# LED.net
KiCad netlist of a schematic drawn in Altium Designer
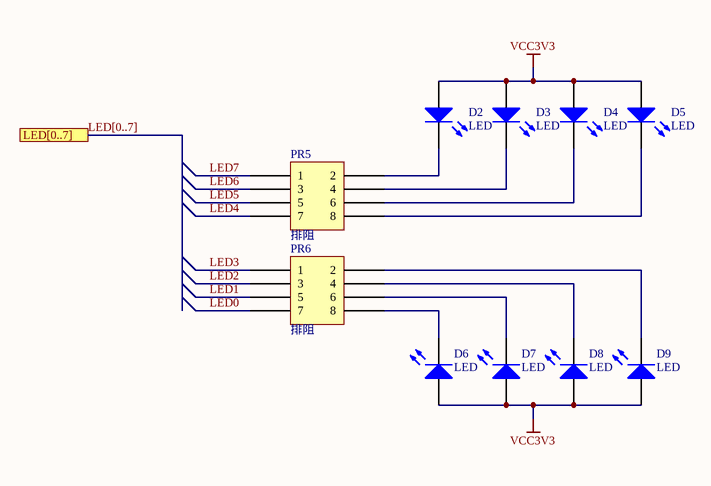
[diagram p0: LED.SchDoc]

(export (version "E")
  (design (tool "Eeschema 10.0.6"))
  (components
    (comp (ref "D2") (value "LED") (footprint "LED0805") (libsource (lib "常用原件") (part "LED")))
    (comp (ref "D3") (value "LED") (footprint "LED0805") (libsource (lib "常用原件") (part "LED")))
    (comp (ref "D4") (value "LED") (footprint "LED0805") (libsource (lib "常用原件") (part "LED")))
    (comp (ref "D5") (value "LED") (footprint "LED0805") (libsource (lib "常用原件") (part "LED")))
    (comp (ref "D6") (value "LED") (footprint "LED0805") (libsource (lib "常用原件") (part "LED")))
    (comp (ref "D7") (value "LED") (footprint "LED0805") (libsource (lib "常用原件") (part "LED")))
    (comp (ref "D8") (value "LED") (footprint "LED0805") (libsource (lib "常用原件") (part "LED")))
    (comp (ref "D9") (value "LED") (footprint "LED0805") (libsource (lib "常用原件") (part "LED")))
    (comp (ref "PR5") (value "排阻") (footprint "8P4R-0603") (libsource (lib "Schlib1") (part "RES*4")))
    (comp (ref "PR6") (value "排阻") (footprint "8P4R-0603") (libsource (lib "Schlib1") (part "RES*4")))
  )
  (nets
    (net (code "1") (name "/LED0") (class "Default")
      (node (ref "PR6") (pin "7") (pinfunction "7_7") (pintype "passive"))
    )
    (net (code "2") (name "/LED1") (class "Default")
      (node (ref "PR6") (pin "5") (pinfunction "5_5") (pintype "passive"))
    )
    (net (code "3") (name "/LED2") (class "Default")
      (node (ref "PR6") (pin "3") (pinfunction "3_3") (pintype "passive"))
    )
    (net (code "4") (name "/LED3") (class "Default")
      (node (ref "PR6") (pin "1") (pinfunction "1_1") (pintype "passive"))
    )
    (net (code "5") (name "/LED4") (class "Default")
      (node (ref "PR5") (pin "7") (pinfunction "7_7") (pintype "passive"))
    )
    (net (code "6") (name "/LED5") (class "Default")
      (node (ref "PR5") (pin "5") (pinfunction "5_5") (pintype "passive"))
    )
    (net (code "7") (name "/LED6") (class "Default")
      (node (ref "PR5") (pin "3") (pinfunction "3_3") (pintype "passive"))
    )
    (net (code "8") (name "/LED7") (class "Default")
      (node (ref "PR5") (pin "1") (pinfunction "1_1") (pintype "passive"))
    )
    (net (code "10") (name "Net-(D2-K)") (class "Default")
      (node (ref "D2") (pin "1") (pinfunction "K_1") (pintype "passive"))
      (node (ref "PR5") (pin "2") (pinfunction "2_2") (pintype "passive"))
    )
    (net (code "11") (name "Net-(D3-K)") (class "Default")
      (node (ref "D3") (pin "1") (pinfunction "K_1") (pintype "passive"))
      (node (ref "PR5") (pin "4") (pinfunction "4_4") (pintype "passive"))
    )
    (net (code "12") (name "Net-(D4-K)") (class "Default")
      (node (ref "D4") (pin "1") (pinfunction "K_1") (pintype "passive"))
      (node (ref "PR5") (pin "6") (pinfunction "6_6") (pintype "passive"))
    )
    (net (code "13") (name "Net-(D5-K)") (class "Default")
      (node (ref "D5") (pin "1") (pinfunction "K_1") (pintype "passive"))
      (node (ref "PR5") (pin "8") (pinfunction "8_8") (pintype "passive"))
    )
    (net (code "14") (name "Net-(D6-K)") (class "Default")
      (node (ref "D6") (pin "1") (pinfunction "K_1") (pintype "passive"))
      (node (ref "PR6") (pin "8") (pinfunction "8_8") (pintype "passive"))
    )
    (net (code "15") (name "Net-(D7-K)") (class "Default")
      (node (ref "D7") (pin "1") (pinfunction "K_1") (pintype "passive"))
      (node (ref "PR6") (pin "6") (pinfunction "6_6") (pintype "passive"))
    )
    (net (code "16") (name "Net-(D8-K)") (class "Default")
      (node (ref "D8") (pin "1") (pinfunction "K_1") (pintype "passive"))
      (node (ref "PR6") (pin "4") (pinfunction "4_4") (pintype "passive"))
    )
    (net (code "17") (name "Net-(D9-K)") (class "Default")
      (node (ref "D9") (pin "1") (pinfunction "K_1") (pintype "passive"))
      (node (ref "PR6") (pin "2") (pinfunction "2_2") (pintype "passive"))
    )
    (net (code "18") (name "VCC3V3") (class "Default")
      (node (ref "D2") (pin "2") (pinfunction "A_2") (pintype "passive"))
      (node (ref "D3") (pin "2") (pinfunction "A_2") (pintype "passive"))
      (node (ref "D4") (pin "2") (pinfunction "A_2") (pintype "passive"))
      (node (ref "D5") (pin "2") (pinfunction "A_2") (pintype "passive"))
      (node (ref "D6") (pin "2") (pinfunction "A_2") (pintype "passive"))
      (node (ref "D7") (pin "2") (pinfunction "A_2") (pintype "passive"))
      (node (ref "D8") (pin "2") (pinfunction "A_2") (pintype "passive"))
      (node (ref "D9") (pin "2") (pinfunction "A_2") (pintype "passive"))
    )
  )
)
